# Main.net
KiCad netlist of a schematic drawn in Altium Designer
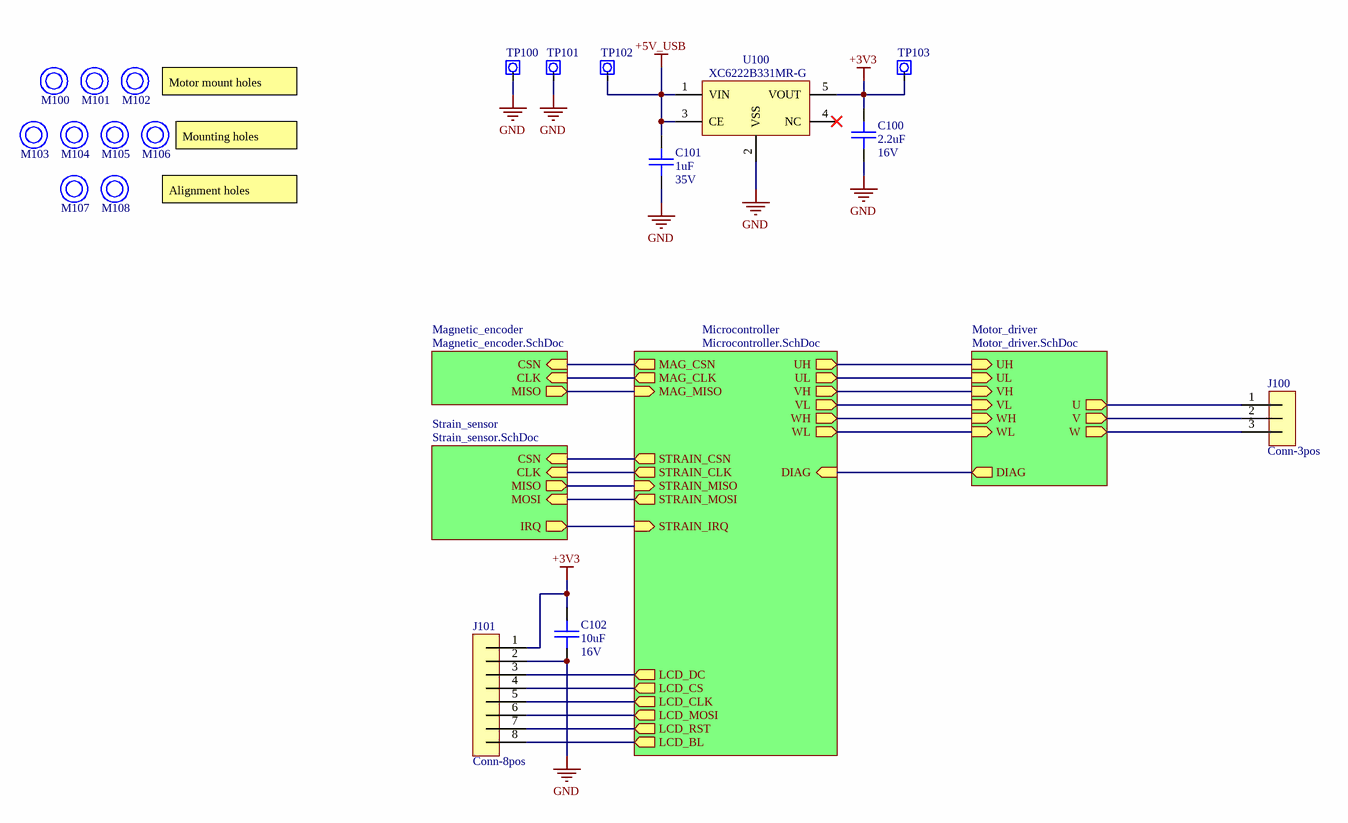
[diagram p0: Main.SchDoc]

(export (version "E")
  (design (tool "Eeschema 10.0.6"))
  (components
    (comp (ref "C100")
      (value "2.2uF")
      (footprint "C0805")
      (description "General purpose ceramic capacitor")
      (fields
        (field (name "VOLTAGE") "16V")
        (field (name "MANUFACTURER") "TDK Corporation")
        (field (name "MANUFACTURER PART NO") "CGA4J3X7R1C225K125AB")
      )
      (libsource (lib "Moonlight_Library") (part "CAP"))
    )
    (comp (ref "C101")
      (value "1uF")
      (footprint "C0603")
      (description "General purpose ceramic capacitor")
      (fields
        (field (name "VOLTAGE") "35V")
        (field (name "MANUFACTURER") "TDK Corporation")
        (field (name "MANUFACTURER PART NO") "CGA3E1X7R1V105K080AC")
      )
      (libsource (lib "Moonlight_Library") (part "CAP"))
    )
    (comp (ref "C102")
      (value "10uF")
      (footprint "C0805")
      (description "General purpose ceramic capacitor")
      (fields
        (field (name "VOLTAGE") "16V")
        (field (name "MANUFACTURER") "TDK Corporation")
        (field (name "MANUFACTURER PART NO") "CGA4J1X7S1C106K125AC")
      )
      (libsource (lib "Moonlight_Library") (part "CAP"))
    )
    (comp (ref "J100")
      (value "Conn-3pos")
      (footprint "0532610371")
      (description "3 pin horizontal picoblade connector")
      (fields (field (name "MANUFACTURER") "Molex") (field (name "MANUFACTURER PART NO") "0532610371"))
      (libsource (lib "Moonlight_Library") (part "Conn-3pos"))
    )
    (comp (ref "J101")
      (value "Conn-8pos")
      (footprint "2mm_pads_8")
      (description "2mm pitch solder pads")
      (fields (field (name "MANUFACTURER PART NO") "2mm_pads_8"))
      (libsource (lib "Moonlight_Library") (part "Conn-8pos"))
    )
    (comp (ref "M100")
      (value "Mounting_Hole_Unplated")
      (footprint "M1.6_Close_Unplated")
      (description "M1.6 Hole, Unplated")
      (libsource (lib "Moonlight_Library") (part "Mounting_Hole_Unplated"))
    )
    (comp (ref "M101")
      (value "Mounting_Hole_Unplated")
      (footprint "M1.6_Close_Unplated")
      (description "M1.6 Hole, Unplated")
      (libsource (lib "Moonlight_Library") (part "Mounting_Hole_Unplated"))
    )
    (comp (ref "M102")
      (value "Mounting_Hole_Unplated")
      (footprint "M1.6_Close_Unplated")
      (description "M1.6 Hole, Unplated")
      (libsource (lib "Moonlight_Library") (part "Mounting_Hole_Unplated"))
    )
    (comp (ref "M103")
      (value "Mounting_Hole_Unplated")
      (footprint "M2_Normal_Unplated")
      (description "M2 Hole, Unplated")
      (libsource (lib "Moonlight_Library") (part "Mounting_Hole_Unplated"))
    )
    (comp (ref "M104")
      (value "Mounting_Hole_Unplated")
      (footprint "M2_Normal_Unplated")
      (description "M2 Hole, Unplated")
      (libsource (lib "Moonlight_Library") (part "Mounting_Hole_Unplated"))
    )
    (comp (ref "M105")
      (value "Mounting_Hole_Unplated")
      (footprint "M2_Normal_Unplated")
      (description "M2 Hole, Unplated")
      (libsource (lib "Moonlight_Library") (part "Mounting_Hole_Unplated"))
    )
    (comp (ref "M106")
      (value "Mounting_Hole_Unplated")
      (footprint "M2_Normal_Unplated")
      (description "M2 Hole, Unplated")
      (libsource (lib "Moonlight_Library") (part "Mounting_Hole_Unplated"))
    )
    (comp (ref "M107")
      (value "Mounting_Hole_Unplated")
      (footprint "M2_Close_Unplated")
      (description "M2 Hole, Unplated")
      (libsource (lib "Moonlight_Library") (part "Mounting_Hole_Unplated"))
    )
    (comp (ref "M108")
      (value "Mounting_Hole_Unplated")
      (footprint "M2_Close_Unplated")
      (description "M2 Hole, Unplated")
      (libsource (lib "Moonlight_Library") (part "Mounting_Hole_Unplated"))
    )
    (comp (ref "TP100")
      (value "Testpoint")
      (footprint "5019")
      (description "SMD Testpoint, loop style")
      (fields
        (field (name "MANUFACTURER") "Keystone Electronics")
        (field (name "MANUFACTURER PART NO") "5019")
      )
      (libsource (lib "Moonlight_Library") (part "Testpoint"))
    )
    (comp (ref "TP101")
      (value "Testpoint")
      (footprint "5019")
      (description "SMD Testpoint, loop style")
      (fields
        (field (name "MANUFACTURER") "Keystone Electronics")
        (field (name "MANUFACTURER PART NO") "5019")
      )
      (libsource (lib "Moonlight_Library") (part "Testpoint"))
    )
    (comp (ref "TP102")
      (value "Testpoint")
      (footprint "5019")
      (description "SMD Testpoint, loop style")
      (fields
        (field (name "MANUFACTURER") "Keystone Electronics")
        (field (name "MANUFACTURER PART NO") "5019")
      )
      (libsource (lib "Moonlight_Library") (part "Testpoint"))
    )
    (comp (ref "TP103")
      (value "Testpoint")
      (footprint "5019")
      (description "SMD Testpoint, loop style")
      (fields
        (field (name "MANUFACTURER") "Keystone Electronics")
        (field (name "MANUFACTURER PART NO") "5019")
      )
      (libsource (lib "Moonlight_Library") (part "Testpoint"))
    )
    (comp (ref "U100")
      (value "XC6222B331MR-G")
      (footprint "SOT-25-5")
      (description "3.3V 700mA LDO linear regulator")
      (fields
        (field (name "MANUFACTURER") "Torex Semiconductor")
        (field (name "MANUFACTURER PART NO") "XC6222B331MR-G")
      )
      (libsource (lib "Moonlight_Library") (part "XC6222B331MR-G"))
    )
  )
  (nets
    (net (code "1") (name "+3V3") (class "Default")
      (node (ref "C100") (pin "1") (pinfunction "1_1") (pintype "passive"))
      (node (ref "C102") (pin "1") (pinfunction "1_1") (pintype "passive"))
      (node (ref "J101") (pin "1") (pinfunction "1_1") (pintype "passive"))
      (node (ref "TP103") (pin "1") (pinfunction "1_1") (pintype "passive"))
      (node (ref "U100") (pin "5") (pinfunction "VOUT_5") (pintype "passive"))
    )
    (net (code "2") (name "+5V_USB") (class "Default")
      (node (ref "C101") (pin "1") (pinfunction "1_1") (pintype "passive"))
      (node (ref "TP102") (pin "1") (pinfunction "1_1") (pintype "passive"))
      (node (ref "U100") (pin "1") (pinfunction "VIN_1") (pintype "passive"))
      (node (ref "U100") (pin "3") (pinfunction "CE_3") (pintype "passive"))
    )
    (net (code "5") (name "/LCD_BL") (class "Default")
      (node (ref "J101") (pin "8") (pinfunction "8_8") (pintype "passive"))
    )
    (net (code "6") (name "/LCD_CLK") (class "Default")
      (node (ref "J101") (pin "5") (pinfunction "5_5") (pintype "passive"))
    )
    (net (code "7") (name "/LCD_CS") (class "Default")
      (node (ref "J101") (pin "4") (pinfunction "4_4") (pintype "passive"))
    )
    (net (code "8") (name "/LCD_DC") (class "Default")
      (node (ref "J101") (pin "3") (pinfunction "3_3") (pintype "passive"))
    )
    (net (code "9") (name "/LCD_MOSI") (class "Default")
      (node (ref "J101") (pin "6") (pinfunction "6_6") (pintype "passive"))
    )
    (net (code "10") (name "/LCD_RST") (class "Default")
      (node (ref "J101") (pin "7") (pinfunction "7_7") (pintype "passive"))
    )
    (net (code "18") (name "/U") (class "Default")
      (node (ref "J100") (pin "1") (pinfunction "1_1") (pintype "passive"))
    )
    (net (code "21") (name "/V") (class "Default")
      (node (ref "J100") (pin "2") (pinfunction "2_2") (pintype "passive"))
    )
    (net (code "24") (name "/W") (class "Default")
      (node (ref "J100") (pin "3") (pinfunction "3_3") (pintype "passive"))
    )
    (net (code "27") (name "GND") (class "Default")
      (node (ref "C100") (pin "2") (pinfunction "2_2") (pintype "passive"))
      (node (ref "C101") (pin "2") (pinfunction "2_2") (pintype "passive"))
      (node (ref "C102") (pin "2") (pinfunction "2_2") (pintype "passive"))
      (node (ref "J101") (pin "2") (pinfunction "2_2") (pintype "passive"))
      (node (ref "TP100") (pin "1") (pinfunction "1_1") (pintype "passive"))
      (node (ref "TP101") (pin "1") (pinfunction "1_1") (pintype "passive"))
      (node (ref "U100") (pin "2") (pinfunction "VSS_2") (pintype "passive"))
    )
    (net (code "28") (name "unconnected-(U100-NC-Pad4)") (class "Default")
      (node (ref "U100") (pin "4") (pinfunction "NC_4") (pintype "passive+no_connect"))
    )
  )
)
